# 140311_AriloTX_REV2_0_0.net
KiCad netlist of a schematic drawn in EAGLE
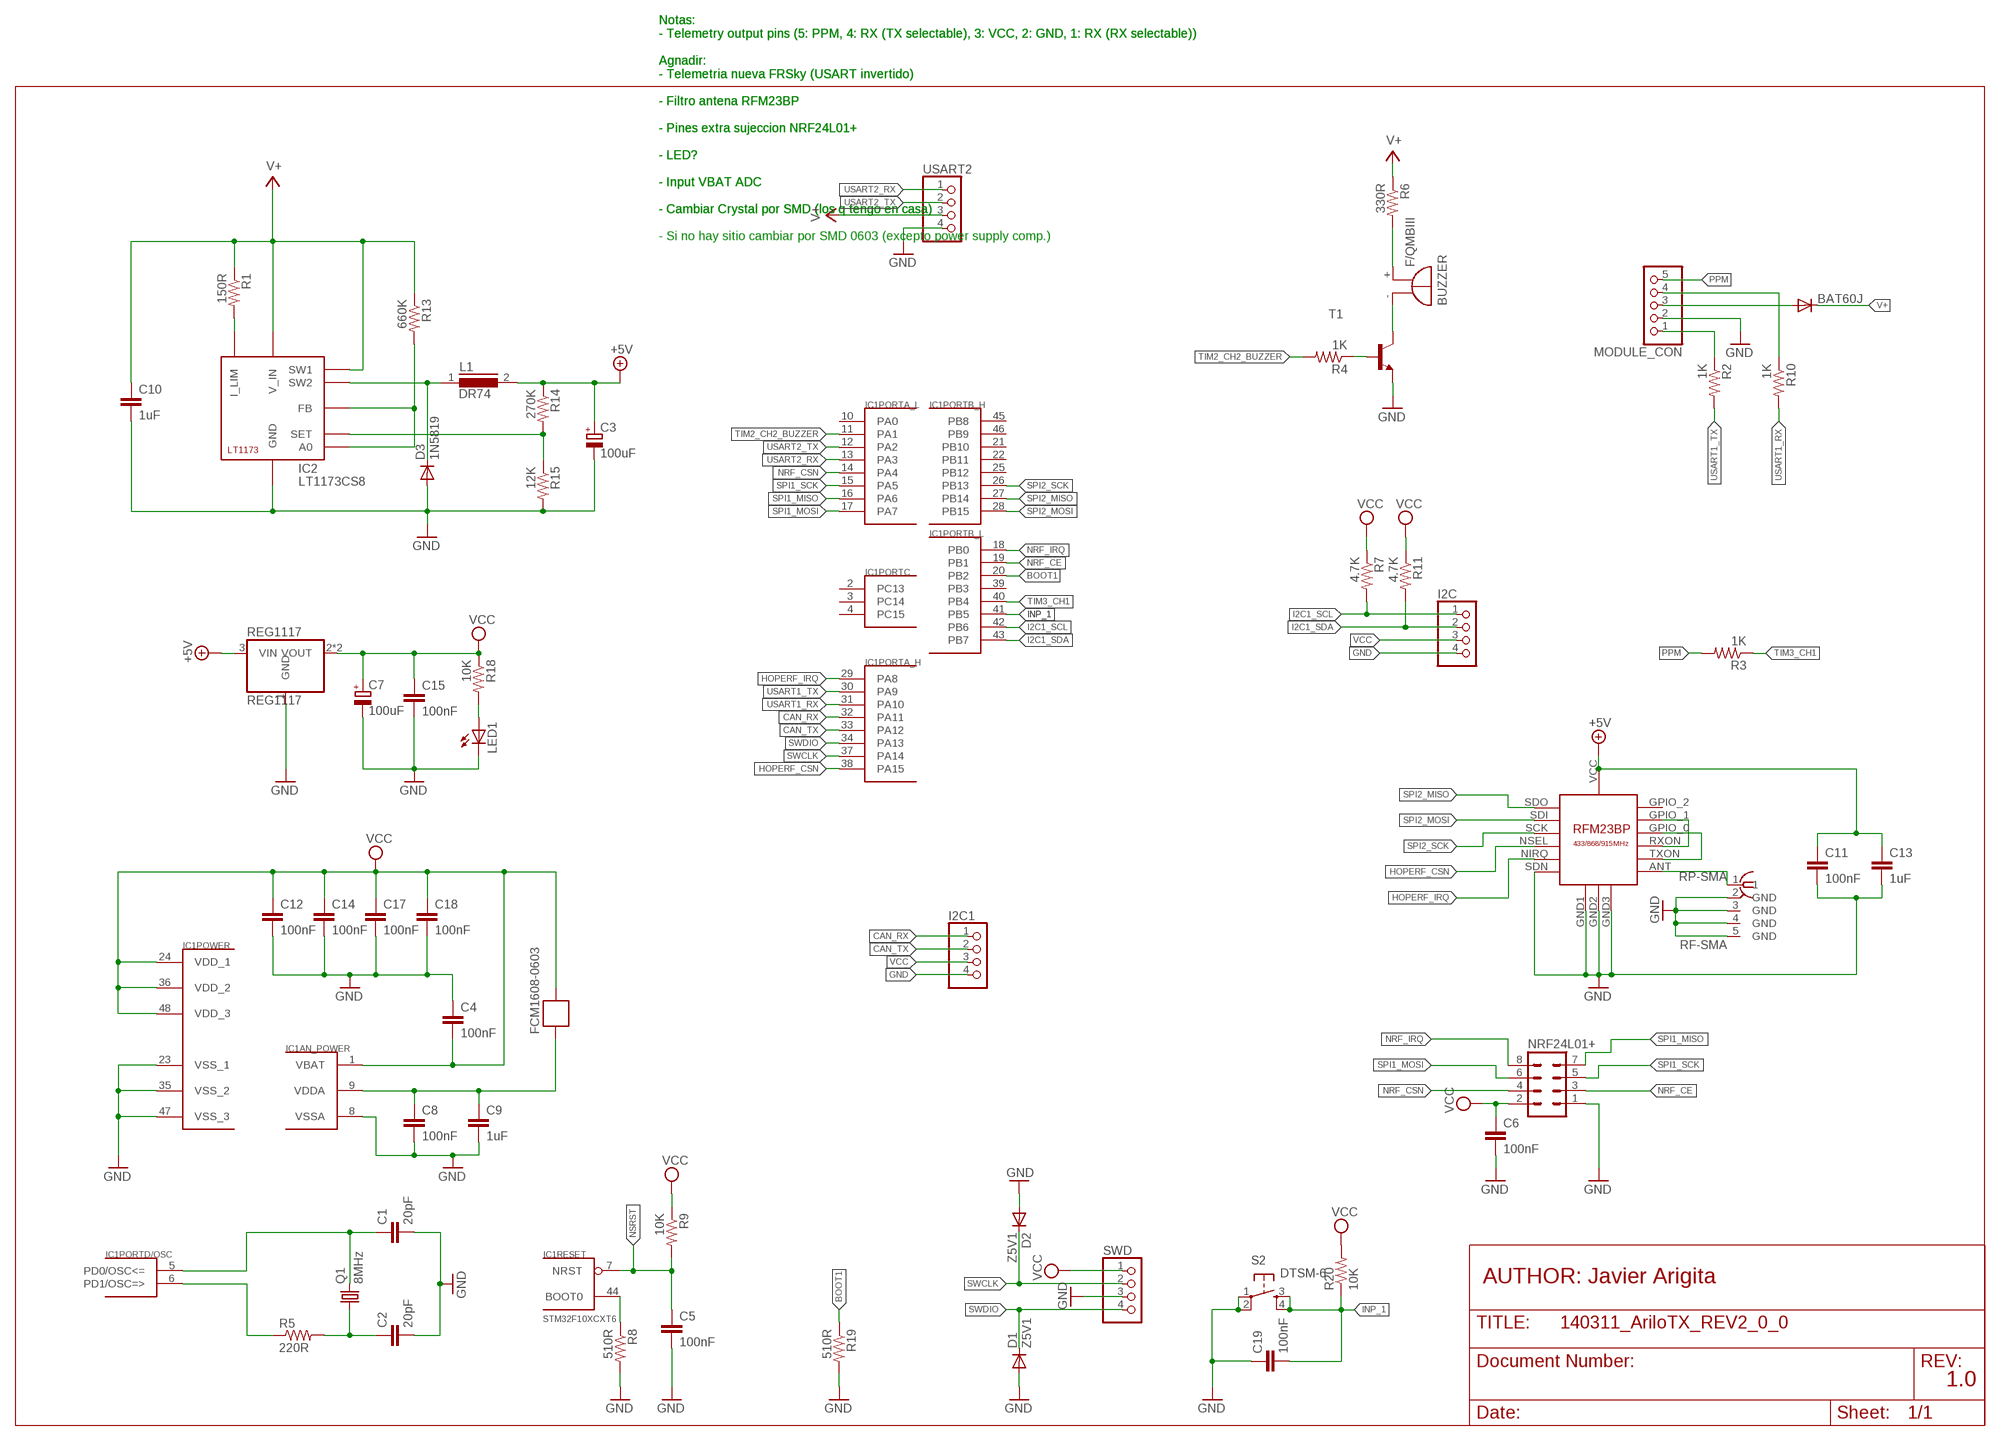
[diagram p0: schematic, sheet 1]

(export (version "E")
  (design (tool "Eeschema 10.0.6"))
  (components
    (comp (ref "BAT60J")
      (value "DIODE-SOD323-R")
      (footprint "eagle-import:SOD323-R")
      (libsource (lib "eagle-import") (part "DIODE-SOD323-R"))
    )
    (comp (ref "BUZZER")
      (value "F/QMBIII")
      (footprint "eagle-import:F_QMBIII")
      (libsource (lib "eagle-import") (part "F/QMBIII"))
    )
    (comp (ref "C1")
      (value "20pF")
      (footprint "eagle-import:C0805")
      (libsource (lib "eagle-import") (part "C-EUC0805"))
    )
    (comp (ref "C2")
      (value "20pF")
      (footprint "eagle-import:C0805")
      (libsource (lib "eagle-import") (part "C-EUC0805"))
    )
    (comp (ref "C3")
      (value "100uF")
      (footprint "eagle-import:SMC_B")
      (libsource (lib "eagle-import") (part "CPOL-EUSMCB"))
    )
    (comp (ref "C4")
      (value "100nF")
      (footprint "eagle-import:C0805")
      (libsource (lib "eagle-import") (part "C-EUC0805"))
    )
    (comp (ref "C5")
      (value "100nF")
      (footprint "eagle-import:C0805")
      (libsource (lib "eagle-import") (part "C-EUC0805"))
    )
    (comp (ref "C6")
      (value "100nF")
      (footprint "eagle-import:C0805")
      (libsource (lib "eagle-import") (part "C-EUC0805"))
    )
    (comp (ref "C7")
      (value "100uF")
      (footprint "eagle-import:SMC_B")
      (libsource (lib "eagle-import") (part "CPOL-EUSMCB"))
    )
    (comp (ref "C8")
      (value "100nF")
      (footprint "eagle-import:C0805")
      (libsource (lib "eagle-import") (part "C-EUC0805"))
    )
    (comp (ref "C9")
      (value "1uF")
      (footprint "eagle-import:C3216")
      (libsource (lib "eagle-import") (part "resistor_C-EUC3216"))
    )
    (comp (ref "C10")
      (value "1uF")
      (footprint "eagle-import:C3216")
      (libsource (lib "eagle-import") (part "resistor_C-EUC3216"))
    )
    (comp (ref "C11")
      (value "100nF")
      (footprint "eagle-import:C0805")
      (libsource (lib "eagle-import") (part "C-EUC0805"))
    )
    (comp (ref "C12")
      (value "100nF")
      (footprint "eagle-import:C0805")
      (libsource (lib "eagle-import") (part "C-EUC0805"))
    )
    (comp (ref "C13")
      (value "1uF")
      (footprint "eagle-import:C3216")
      (libsource (lib "eagle-import") (part "resistor_C-EUC3216"))
    )
    (comp (ref "C14")
      (value "100nF")
      (footprint "eagle-import:C0805")
      (libsource (lib "eagle-import") (part "C-EUC0805"))
    )
    (comp (ref "C15")
      (value "100nF")
      (footprint "eagle-import:C0805")
      (libsource (lib "eagle-import") (part "C-EUC0805"))
    )
    (comp (ref "C17")
      (value "100nF")
      (footprint "eagle-import:C0805")
      (libsource (lib "eagle-import") (part "C-EUC0805"))
    )
    (comp (ref "C18")
      (value "100nF")
      (footprint "eagle-import:C0805")
      (libsource (lib "eagle-import") (part "C-EUC0805"))
    )
    (comp (ref "C19")
      (value "100nF")
      (footprint "eagle-import:C0805")
      (libsource (lib "eagle-import") (part "C-EUC0805"))
    )
    (comp (ref "D1")
      (value "Z5V1")
      (footprint "eagle-import:SOD323-R")
      (libsource (lib "eagle-import") (part "DIODE-SOD323-R"))
    )
    (comp (ref "D2")
      (value "Z5V1")
      (footprint "eagle-import:SOD323-R")
      (libsource (lib "eagle-import") (part "DIODE-SOD323-R"))
    )
    (comp (ref "D3")
      (value "1N5819")
      (footprint "eagle-import:DO214AC")
      (libsource (lib "eagle-import") (part "DIODE-DO214AC"))
    )
    (comp (ref "FCM1608-0603")
      (value "FERRITE-BEAD")
      (footprint "eagle-import:R0603")
      (libsource (lib "eagle-import") (part "FERRITE-BEAD"))
    )
    (comp (ref "I2C")
      (value "PINHD-1X4")
      (footprint "eagle-import:1X04")
      (libsource (lib "eagle-import") (part "PINHD-1X4"))
    )
    (comp (ref "I2C1")
      (value "PINHD-1X4")
      (footprint "eagle-import:1X04")
      (libsource (lib "eagle-import") (part "PINHD-1X4"))
    )
    (comp (ref "IC1")
      (value "STM32F10XCXT6")
      (footprint "eagle-import:TQFP48")
      (libsource (lib "eagle-import") (part "STM32F10XCXT6"))
    )
    (comp (ref "IC2")
      (value "LT1173CS8")
      (footprint "eagle-import:SOIC8")
      (libsource (lib "eagle-import") (part "LT1173CS8"))
    )
    (comp (ref "L1")
      (value "DR74")
      (footprint "eagle-import:DR74")
      (libsource (lib "eagle-import") (part "DR74"))
    )
    (comp (ref "LED1")
      (value "LED0805")
      (footprint "eagle-import:CHIPLED_0805")
      (libsource (lib "eagle-import") (part "LED0805"))
    )
    (comp (ref "MODULE_CON")
      (value "PINHD-1X5")
      (footprint "eagle-import:1X05")
      (libsource (lib "eagle-import") (part "PINHD-1X5"))
    )
    (comp (ref "NRF24L01+")
      (value "MA04-2")
      (footprint "eagle-import:MA04-2")
      (libsource (lib "eagle-import") (part "MA04-2"))
    )
    (comp (ref "Q1")
      (value "8MHz")
      (footprint "eagle-import:SM49")
      (libsource (lib "eagle-import") (part "CRYSTALSM49"))
    )
    (comp (ref "R1")
      (value "150R")
      (footprint "eagle-import:R0805")
      (libsource (lib "eagle-import") (part "RESISTOR0805"))
    )
    (comp (ref "R2")
      (value "1K")
      (footprint "eagle-import:R0805")
      (libsource (lib "eagle-import") (part "RESISTOR0805"))
    )
    (comp (ref "R3")
      (value "1K")
      (footprint "eagle-import:R0805")
      (libsource (lib "eagle-import") (part "RESISTOR0805"))
    )
    (comp (ref "R4")
      (value "1K")
      (footprint "eagle-import:R0805")
      (libsource (lib "eagle-import") (part "RESISTOR0805"))
    )
    (comp (ref "R5")
      (value "220R")
      (footprint "eagle-import:R0805")
      (libsource (lib "eagle-import") (part "RESISTOR0805"))
    )
    (comp (ref "R6")
      (value "330R")
      (footprint "eagle-import:R0805")
      (libsource (lib "eagle-import") (part "RESISTOR0805"))
    )
    (comp (ref "R7")
      (value "4.7K")
      (footprint "eagle-import:R0805")
      (libsource (lib "eagle-import") (part "RESISTOR0805"))
    )
    (comp (ref "R8")
      (value "510R")
      (footprint "eagle-import:R0805")
      (libsource (lib "eagle-import") (part "RESISTOR0805"))
    )
    (comp (ref "R9")
      (value "10K")
      (footprint "eagle-import:R0805")
      (libsource (lib "eagle-import") (part "RESISTOR0805"))
    )
    (comp (ref "R10")
      (value "1K")
      (footprint "eagle-import:R0805")
      (libsource (lib "eagle-import") (part "RESISTOR0805"))
    )
    (comp (ref "R11")
      (value "4.7K")
      (footprint "eagle-import:R0805")
      (libsource (lib "eagle-import") (part "RESISTOR0805"))
    )
    (comp (ref "R13")
      (value "660K")
      (footprint "eagle-import:R0805")
      (libsource (lib "eagle-import") (part "RESISTOR0805"))
    )
    (comp (ref "R14")
      (value "270K")
      (footprint "eagle-import:R0805")
      (libsource (lib "eagle-import") (part "RESISTOR0805"))
    )
    (comp (ref "R15")
      (value "12K")
      (footprint "eagle-import:R0805")
      (libsource (lib "eagle-import") (part "RESISTOR0805"))
    )
    (comp (ref "R18")
      (value "10K")
      (footprint "eagle-import:R0805")
      (libsource (lib "eagle-import") (part "RESISTOR0805"))
    )
    (comp (ref "R19")
      (value "510R")
      (footprint "eagle-import:R0805")
      (libsource (lib "eagle-import") (part "RESISTOR0805"))
    )
    (comp (ref "R20")
      (value "10K")
      (footprint "eagle-import:R0805")
      (libsource (lib "eagle-import") (part "RESISTOR0805"))
    )
    (comp (ref "REG1117")
      (value "REG1117")
      (footprint "eagle-import:SOT223")
      (libsource (lib "eagle-import") (part "REG1117"))
    )
    (comp (ref "RP-SMA")
      (value "RF-SMA")
      (footprint "eagle-import:BU-SMA-H")
      (libsource (lib "eagle-import") (part "RF-SMA"))
    )
    (comp (ref "S2")
      (value "DTSM-6")
      (footprint "eagle-import:DTSM-6")
      (libsource (lib "eagle-import") (part "DTSM-6"))
    )
    (comp (ref "SWD")
      (value "PINHD-1X4")
      (footprint "eagle-import:1X04")
      (libsource (lib "eagle-import") (part "PINHD-1X4"))
    )
    (comp (ref "T1")
      (value "BC848-NPN-SOT23-BEC")
      (footprint "eagle-import:SOT23-BEC")
      (libsource (lib "eagle-import") (part "-NPN-SOT23-BECBC848"))
    )
    (comp (ref "U$1")
      (value "RFM23BP")
      (footprint "eagle-import:RFM23BP")
      (libsource (lib "eagle-import") (part "RFM23BP"))
    )
    (comp (ref "USART2")
      (value "PINHD-1X4")
      (footprint "eagle-import:1X04")
      (libsource (lib "eagle-import") (part "PINHD-1X4"))
    )
  )
  (nets
    (net (code "1") (name "+5V") (class "Default")
      (node (ref "C11") (pin "1") (pinfunction "1_1") (pintype "passive"))
      (node (ref "C13") (pin "1") (pinfunction "1_1") (pintype "passive"))
      (node (ref "C3") (pin "+") (pinfunction "+_+") (pintype "passive"))
      (node (ref "L1") (pin "2") (pinfunction "2_2") (pintype "passive"))
      (node (ref "R14") (pin "1") (pinfunction "1_1") (pintype "passive"))
      (node (ref "REG1117") (pin "3") (pinfunction "VIN_3") (pintype "input"))
      (node (ref "U$1") (pin "VCC") (pinfunction "VCC_VCC") (pintype "power_in"))
    )
    (net (code "2") (name "BOOT1") (class "Default")
      (node (ref "IC1") (pin "20") (pinfunction "PB2_20") (pintype "bidirectional"))
      (node (ref "R19") (pin "1") (pinfunction "1_1") (pintype "passive"))
    )
    (net (code "3") (name "CAN_RX") (class "Default")
      (node (ref "I2C1") (pin "1") (pinfunction "1_1") (pintype "passive"))
      (node (ref "IC1") (pin "32") (pinfunction "PA11_32") (pintype "bidirectional"))
    )
    (net (code "4") (name "CAN_TX") (class "Default")
      (node (ref "I2C1") (pin "2") (pinfunction "2_2") (pintype "passive"))
      (node (ref "IC1") (pin "33") (pinfunction "PA12_33") (pintype "bidirectional"))
    )
    (net (code "5") (name "GND") (class "Default")
      (node (ref "C1") (pin "2") (pinfunction "2_2") (pintype "passive"))
      (node (ref "C10") (pin "2") (pinfunction "2_2") (pintype "passive"))
      (node (ref "C11") (pin "2") (pinfunction "2_2") (pintype "passive"))
      (node (ref "C12") (pin "2") (pinfunction "2_2") (pintype "passive"))
      (node (ref "C13") (pin "2") (pinfunction "2_2") (pintype "passive"))
      (node (ref "C14") (pin "2") (pinfunction "2_2") (pintype "passive"))
      (node (ref "C15") (pin "2") (pinfunction "2_2") (pintype "passive"))
      (node (ref "C17") (pin "2") (pinfunction "2_2") (pintype "passive"))
      (node (ref "C18") (pin "2") (pinfunction "2_2") (pintype "passive"))
      (node (ref "C19") (pin "1") (pinfunction "1_1") (pintype "passive"))
      (node (ref "C2") (pin "2") (pinfunction "2_2") (pintype "passive"))
      (node (ref "C3") (pin "-") (pinfunction "-_-") (pintype "passive"))
      (node (ref "C4") (pin "1") (pinfunction "1_1") (pintype "passive"))
      (node (ref "C5") (pin "2") (pinfunction "2_2") (pintype "passive"))
      (node (ref "C6") (pin "2") (pinfunction "2_2") (pintype "passive"))
      (node (ref "C7") (pin "-") (pinfunction "-_-") (pintype "passive"))
      (node (ref "C8") (pin "2") (pinfunction "2_2") (pintype "passive"))
      (node (ref "C9") (pin "2") (pinfunction "2_2") (pintype "passive"))
      (node (ref "D1") (pin "A") (pinfunction "A_A") (pintype "passive"))
      (node (ref "D2") (pin "A") (pinfunction "A_A") (pintype "passive"))
      (node (ref "D3") (pin "A") (pinfunction "A_A") (pintype "passive"))
      (node (ref "I2C") (pin "4") (pinfunction "4_4") (pintype "passive"))
      (node (ref "I2C1") (pin "4") (pinfunction "4_4") (pintype "passive"))
      (node (ref "IC1") (pin "23") (pinfunction "VSS_1_23") (pintype "power_in"))
      (node (ref "IC1") (pin "35") (pinfunction "VSS_2_35") (pintype "power_in"))
      (node (ref "IC1") (pin "47") (pinfunction "VSS_3_47") (pintype "power_in"))
      (node (ref "IC1") (pin "8") (pinfunction "VSSA_8") (pintype "power_in"))
      (node (ref "IC2") (pin "5") (pinfunction "GND_5") (pintype "power_in"))
      (node (ref "LED1") (pin "C") (pinfunction "C_C") (pintype "passive"))
      (node (ref "MODULE_CON") (pin "2") (pinfunction "2_2") (pintype "passive"))
      (node (ref "NRF24L01+") (pin "1") (pinfunction "1_1") (pintype "passive"))
      (node (ref "R15") (pin "2") (pinfunction "2_2") (pintype "passive"))
      (node (ref "R19") (pin "2") (pinfunction "2_2") (pintype "passive"))
      (node (ref "R8") (pin "2") (pinfunction "2_2") (pintype "passive"))
      (node (ref "REG1117") (pin "1") (pinfunction "GND_1") (pintype "power_in"))
      (node (ref "RP-SMA") (pin "2") (pinfunction "GND_2") (pintype "power_in"))
      (node (ref "RP-SMA") (pin "3") (pinfunction "GND_3") (pintype "bidirectional"))
      (node (ref "RP-SMA") (pin "4") (pinfunction "GND_4") (pintype "bidirectional"))
      (node (ref "RP-SMA") (pin "5") (pinfunction "GND_5") (pintype "bidirectional"))
      (node (ref "S2") (pin "1") (pinfunction "1_1") (pintype "passive"))
      (node (ref "S2") (pin "2") (pinfunction "2_2") (pintype "passive"))
      (node (ref "SWD") (pin "3") (pinfunction "3_3") (pintype "passive"))
      (node (ref "T1") (pin "E") (pinfunction "E_E") (pintype "passive"))
      (node (ref "U$1") (pin "GND1") (pinfunction "GND1_GND1") (pintype "power_in"))
      (node (ref "U$1") (pin "GND2") (pinfunction "GND2_GND2") (pintype "power_in"))
      (node (ref "U$1") (pin "GND3") (pinfunction "GND3_GND3") (pintype "power_in"))
      (node (ref "U$1") (pin "SDN") (pinfunction "SDN_SDN") (pintype "bidirectional"))
      (node (ref "USART2") (pin "4") (pinfunction "4_4") (pintype "passive"))
    )
    (net (code "6") (name "HOPERF_CSN") (class "Default")
      (node (ref "IC1") (pin "38") (pinfunction "PA15_38") (pintype "bidirectional"))
      (node (ref "U$1") (pin "NSEL") (pinfunction "NSEL_NSEL") (pintype "bidirectional"))
    )
    (net (code "7") (name "HOPERF_IRQ") (class "Default")
      (node (ref "IC1") (pin "29") (pinfunction "PA8_29") (pintype "bidirectional"))
      (node (ref "U$1") (pin "NIRQ") (pinfunction "NIRQ_NIRQ") (pintype "bidirectional"))
    )
    (net (code "8") (name "I2C1_SCL") (class "Default")
      (node (ref "I2C") (pin "1") (pinfunction "1_1") (pintype "passive"))
      (node (ref "IC1") (pin "42") (pinfunction "PB6_42") (pintype "bidirectional"))
      (node (ref "R7") (pin "2") (pinfunction "2_2") (pintype "passive"))
    )
    (net (code "9") (name "I2C1_SDA") (class "Default")
      (node (ref "I2C") (pin "2") (pinfunction "2_2") (pintype "passive"))
      (node (ref "IC1") (pin "43") (pinfunction "PB7_43") (pintype "bidirectional"))
      (node (ref "R11") (pin "2") (pinfunction "2_2") (pintype "passive"))
    )
    (net (code "10") (name "INP_1") (class "Default")
      (node (ref "C19") (pin "2") (pinfunction "2_2") (pintype "passive"))
      (node (ref "IC1") (pin "41") (pinfunction "PB5_41") (pintype "bidirectional"))
      (node (ref "R20") (pin "1") (pinfunction "1_1") (pintype "passive"))
      (node (ref "S2") (pin "3") (pinfunction "3_3") (pintype "passive"))
      (node (ref "S2") (pin "4") (pinfunction "4_4") (pintype "passive"))
    )
    (net (code "11") (name "NRF_CE") (class "Default")
      (node (ref "IC1") (pin "19") (pinfunction "PB1_19") (pintype "bidirectional"))
      (node (ref "NRF24L01+") (pin "3") (pinfunction "3_3") (pintype "passive"))
    )
    (net (code "12") (name "NRF_CSN") (class "Default")
      (node (ref "IC1") (pin "14") (pinfunction "PA4_14") (pintype "bidirectional"))
      (node (ref "NRF24L01+") (pin "4") (pinfunction "4_4") (pintype "passive"))
    )
    (net (code "13") (name "NRF_IRQ") (class "Default")
      (node (ref "IC1") (pin "18") (pinfunction "PB0_18") (pintype "bidirectional"))
      (node (ref "NRF24L01+") (pin "8") (pinfunction "8_8") (pintype "passive"))
    )
    (net (code "14") (name "NSRST") (class "Default")
      (node (ref "C5") (pin "1") (pinfunction "1_1") (pintype "passive"))
      (node (ref "IC1") (pin "7") (pinfunction "NRST_7") (pintype "input"))
      (node (ref "R9") (pin "2") (pinfunction "2_2") (pintype "passive"))
    )
    (net (code "15") (name "Net-(BAT60J-PadA)") (class "Default")
      (node (ref "BAT60J") (pin "A") (pinfunction "A_A") (pintype "passive"))
      (node (ref "MODULE_CON") (pin "3") (pinfunction "3_3") (pintype "passive"))
    )
    (net (code "16") (name "Net-(BUZZER-+)") (class "Default")
      (node (ref "BUZZER") (pin "-") (pinfunction "+_-") (pintype "passive"))
      (node (ref "T1") (pin "C") (pinfunction "C_C") (pintype "passive"))
    )
    (net (code "17") (name "Net-(BUZZER--)") (class "Default")
      (node (ref "BUZZER") (pin "+") (pinfunction "-_+") (pintype "passive"))
      (node (ref "R6") (pin "2") (pinfunction "2_2") (pintype "passive"))
    )
    (net (code "18") (name "Net-(C2-Pad1)") (class "Default")
      (node (ref "C2") (pin "1") (pinfunction "1_1") (pintype "passive"))
      (node (ref "Q1") (pin "1") (pinfunction "1_1") (pintype "passive"))
      (node (ref "R5") (pin "2") (pinfunction "2_2") (pintype "passive"))
    )
    (net (code "19") (name "Net-(FCM1608-0603-P$2)") (class "Default")
      (node (ref "C8") (pin "1") (pinfunction "1_1") (pintype "passive"))
      (node (ref "C9") (pin "1") (pinfunction "1_1") (pintype "passive"))
      (node (ref "FCM1608-0603") (pin "2") (pinfunction "P$2_2") (pintype "bidirectional"))
      (node (ref "IC1") (pin "9") (pinfunction "VDDA_9") (pintype "power_in"))
    )
    (net (code "20") (name "Net-(IC1G-PD0{slash}OSC<=)") (class "Default")
      (node (ref "C1") (pin "1") (pinfunction "1_1") (pintype "passive"))
      (node (ref "IC1") (pin "5") (pinfunction "PD0/OSC<=_5") (pintype "bidirectional"))
      (node (ref "Q1") (pin "2") (pinfunction "2_2") (pintype "passive"))
    )
    (net (code "21") (name "Net-(IC1G-PD1{slash}OSC=>)") (class "Default")
      (node (ref "IC1") (pin "6") (pinfunction "PD1/OSC=>_6") (pintype "bidirectional"))
      (node (ref "R5") (pin "1") (pinfunction "1_1") (pintype "passive"))
    )
    (net (code "22") (name "Net-(IC1I-BOOT0)") (class "Default")
      (node (ref "IC1") (pin "44") (pinfunction "BOOT0_44") (pintype "input"))
      (node (ref "R8") (pin "1") (pinfunction "1_1") (pintype "passive"))
    )
    (net (code "23") (name "Net-(IC2-A0)") (class "Default")
      (node (ref "IC2") (pin "6") (pinfunction "A0_6") (pintype "passive"))
      (node (ref "IC2") (pin "8") (pinfunction "FB_8") (pintype "passive"))
      (node (ref "R13") (pin "2") (pinfunction "2_2") (pintype "passive"))
    )
    (net (code "24") (name "Net-(IC2-I_LIM)") (class "Default")
      (node (ref "IC2") (pin "1") (pinfunction "I_LIM_1") (pintype "passive"))
      (node (ref "R1") (pin "2") (pinfunction "2_2") (pintype "passive"))
    )
    (net (code "25") (name "Net-(IC2-SET)") (class "Default")
      (node (ref "IC2") (pin "7") (pinfunction "SET_7") (pintype "passive"))
      (node (ref "R14") (pin "2") (pinfunction "2_2") (pintype "passive"))
      (node (ref "R15") (pin "1") (pinfunction "1_1") (pintype "passive"))
    )
    (net (code "26") (name "Net-(IC2-SW2)") (class "Default")
      (node (ref "D3") (pin "C") (pinfunction "C_C") (pintype "passive"))
      (node (ref "IC2") (pin "4") (pinfunction "SW2_4") (pintype "passive"))
      (node (ref "L1") (pin "1") (pinfunction "1_1") (pintype "passive"))
    )
    (net (code "27") (name "Net-(LED1-PadA)") (class "Default")
      (node (ref "LED1") (pin "A") (pinfunction "A_A") (pintype "passive"))
      (node (ref "R18") (pin "2") (pinfunction "2_2") (pintype "passive"))
    )
    (net (code "28") (name "Net-(MODULE_CON-Pad1)") (class "Default")
      (node (ref "MODULE_CON") (pin "1") (pinfunction "1_1") (pintype "passive"))
      (node (ref "R2") (pin "1") (pinfunction "1_1") (pintype "passive"))
    )
    (net (code "29") (name "Net-(MODULE_CON-Pad4)") (class "Default")
      (node (ref "MODULE_CON") (pin "4") (pinfunction "4_4") (pintype "passive"))
      (node (ref "R10") (pin "1") (pinfunction "1_1") (pintype "passive"))
    )
    (net (code "30") (name "Net-(R4-Pad1)") (class "Default")
      (node (ref "R4") (pin "1") (pinfunction "1_1") (pintype "passive"))
      (node (ref "T1") (pin "B") (pinfunction "B_B") (pintype "passive"))
    )
    (net (code "31") (name "Net-(RP-SMA-Pad1)") (class "Default")
      (node (ref "RP-SMA") (pin "1") (pinfunction "1_1") (pintype "passive"))
      (node (ref "U$1") (pin "ANT") (pinfunction "ANT_ANT") (pintype "bidirectional"))
    )
    (net (code "32") (name "Net-(U$1-PadGPIO_0)") (class "Default")
      (node (ref "U$1") (pin "GPIO_0") (pinfunction "GPIO_0_GPIO_0") (pintype "bidirectional"))
      (node (ref "U$1") (pin "TXON") (pinfunction "TXON_TXON") (pintype "bidirectional"))
    )
    (net (code "33") (name "Net-(U$1-PadGPIO_1)") (class "Default")
      (node (ref "U$1") (pin "GPIO_1") (pinfunction "GPIO_1_GPIO_1") (pintype "bidirectional"))
      (node (ref "U$1") (pin "RXON") (pinfunction "RXON_RXON") (pintype "bidirectional"))
    )
    (net (code "34") (name "PPM") (class "Default")
      (node (ref "MODULE_CON") (pin "5") (pinfunction "5_5") (pintype "passive"))
      (node (ref "R3") (pin "2") (pinfunction "2_2") (pintype "passive"))
    )
    (net (code "35") (name "SPI1_MISO") (class "Default")
      (node (ref "IC1") (pin "16") (pinfunction "PA6_16") (pintype "bidirectional"))
      (node (ref "NRF24L01+") (pin "7") (pinfunction "7_7") (pintype "passive"))
    )
    (net (code "36") (name "SPI1_MOSI") (class "Default")
      (node (ref "IC1") (pin "17") (pinfunction "PA7_17") (pintype "bidirectional"))
      (node (ref "NRF24L01+") (pin "6") (pinfunction "6_6") (pintype "passive"))
    )
    (net (code "37") (name "SPI1_SCK") (class "Default")
      (node (ref "IC1") (pin "15") (pinfunction "PA5_15") (pintype "bidirectional"))
      (node (ref "NRF24L01+") (pin "5") (pinfunction "5_5") (pintype "passive"))
    )
    (net (code "38") (name "SPI2_MISO") (class "Default")
      (node (ref "IC1") (pin "27") (pinfunction "PB14_27") (pintype "bidirectional"))
      (node (ref "U$1") (pin "SDO") (pinfunction "SDO_SDO") (pintype "bidirectional"))
    )
    (net (code "39") (name "SPI2_MOSI") (class "Default")
      (node (ref "IC1") (pin "28") (pinfunction "PB15_28") (pintype "bidirectional"))
      (node (ref "U$1") (pin "SDI") (pinfunction "SDI_SDI") (pintype "bidirectional"))
    )
    (net (code "40") (name "SPI2_SCK") (class "Default")
      (node (ref "IC1") (pin "26") (pinfunction "PB13_26") (pintype "bidirectional"))
      (node (ref "U$1") (pin "SCK") (pinfunction "SCK_SCK") (pintype "bidirectional"))
    )
    (net (code "41") (name "SWCLK") (class "Default")
      (node (ref "D2") (pin "C") (pinfunction "C_C") (pintype "passive"))
      (node (ref "IC1") (pin "37") (pinfunction "PA14_37") (pintype "bidirectional"))
      (node (ref "SWD") (pin "2") (pinfunction "2_2") (pintype "passive"))
    )
    (net (code "42") (name "SWDIO") (class "Default")
      (node (ref "D1") (pin "C") (pinfunction "C_C") (pintype "passive"))
      (node (ref "IC1") (pin "34") (pinfunction "PA13_34") (pintype "bidirectional"))
      (node (ref "SWD") (pin "4") (pinfunction "4_4") (pintype "passive"))
    )
    (net (code "43") (name "TIM2_CH2_BUZZER") (class "Default")
      (node (ref "IC1") (pin "11") (pinfunction "PA1_11") (pintype "bidirectional"))
      (node (ref "R4") (pin "2") (pinfunction "2_2") (pintype "passive"))
    )
    (net (code "44") (name "TIM3_CH1") (class "Default")
      (node (ref "IC1") (pin "40") (pinfunction "PB4_40") (pintype "bidirectional"))
      (node (ref "R3") (pin "1") (pinfunction "1_1") (pintype "passive"))
    )
    (net (code "45") (name "USART1_RX") (class "Default")
      (node (ref "IC1") (pin "31") (pinfunction "PA10_31") (pintype "bidirectional"))
      (node (ref "R10") (pin "2") (pinfunction "2_2") (pintype "passive"))
    )
    (net (code "46") (name "USART1_TX") (class "Default")
      (node (ref "IC1") (pin "30") (pinfunction "PA9_30") (pintype "bidirectional"))
      (node (ref "R2") (pin "2") (pinfunction "2_2") (pintype "passive"))
    )
    (net (code "47") (name "USART2_RX") (class "Default")
      (node (ref "IC1") (pin "13") (pinfunction "PA3_13") (pintype "bidirectional"))
      (node (ref "USART2") (pin "1") (pinfunction "1_1") (pintype "passive"))
    )
    (net (code "48") (name "USART2_TX") (class "Default")
      (node (ref "IC1") (pin "12") (pinfunction "PA2_12") (pintype "bidirectional"))
      (node (ref "USART2") (pin "2") (pinfunction "2_2") (pintype "passive"))
    )
    (net (code "49") (name "V+") (class "Default")
      (node (ref "BAT60J") (pin "C") (pinfunction "C_C") (pintype "passive"))
      (node (ref "C10") (pin "1") (pinfunction "1_1") (pintype "passive"))
      (node (ref "IC2") (pin "2") (pinfunction "V_IN_2") (pintype "passive"))
      (node (ref "IC2") (pin "3") (pinfunction "SW1_3") (pintype "passive"))
      (node (ref "R1") (pin "1") (pinfunction "1_1") (pintype "passive"))
      (node (ref "R13") (pin "1") (pinfunction "1_1") (pintype "passive"))
      (node (ref "R6") (pin "1") (pinfunction "1_1") (pintype "passive"))
      (node (ref "USART2") (pin "3") (pinfunction "3_3") (pintype "passive"))
    )
    (net (code "50") (name "VCC") (class "Default")
      (node (ref "C12") (pin "1") (pinfunction "1_1") (pintype "passive"))
      (node (ref "C14") (pin "1") (pinfunction "1_1") (pintype "passive"))
      (node (ref "C15") (pin "1") (pinfunction "1_1") (pintype "passive"))
      (node (ref "C17") (pin "1") (pinfunction "1_1") (pintype "passive"))
      (node (ref "C18") (pin "1") (pinfunction "1_1") (pintype "passive"))
      (node (ref "C4") (pin "2") (pinfunction "2_2") (pintype "passive"))
      (node (ref "C6") (pin "1") (pinfunction "1_1") (pintype "passive"))
      (node (ref "C7") (pin "+") (pinfunction "+_+") (pintype "passive"))
      (node (ref "FCM1608-0603") (pin "1") (pinfunction "P$1_1") (pintype "bidirectional"))
      (node (ref "I2C") (pin "3") (pinfunction "3_3") (pintype "passive"))
      (node (ref "I2C1") (pin "3") (pinfunction "3_3") (pintype "passive"))
      (node (ref "IC1") (pin "1") (pinfunction "VBAT_1") (pintype "power_in"))
      (node (ref "IC1") (pin "24") (pinfunction "VDD_1_24") (pintype "power_in"))
      (node (ref "IC1") (pin "36") (pinfunction "VDD_2_36") (pintype "power_in"))
      (node (ref "IC1") (pin "48") (pinfunction "VDD_3_48") (pintype "power_in"))
      (node (ref "NRF24L01+") (pin "2") (pinfunction "2_2") (pintype "passive"))
      (node (ref "R11") (pin "1") (pinfunction "1_1") (pintype "passive"))
      (node (ref "R18") (pin "1") (pinfunction "1_1") (pintype "passive"))
      (node (ref "R20") (pin "2") (pinfunction "2_2") (pintype "passive"))
      (node (ref "R7") (pin "1") (pinfunction "1_1") (pintype "passive"))
      (node (ref "R9") (pin "1") (pinfunction "1_1") (pintype "passive"))
      (node (ref "REG1117") (pin "2") (pinfunction "VOUT_2") (pintype "power_in"))
      (node (ref "REG1117") (pin "4") (pinfunction "VOUT_4") (pintype "power_in"))
      (node (ref "SWD") (pin "1") (pinfunction "1_1") (pintype "passive"))
    )
    (net (code "51") (name "unconnected-(IC1C-PA0-Pad10)") (class "Default")
      (node (ref "IC1") (pin "10") (pinfunction "PA0_10") (pintype "bidirectional"))
    )
    (net (code "52") (name "unconnected-(IC1D-PB8-Pad45)") (class "Default")
      (node (ref "IC1") (pin "45") (pinfunction "PB8_45") (pintype "bidirectional"))
    )
    (net (code "53") (name "unconnected-(IC1D-PB9-Pad46)") (class "Default")
      (node (ref "IC1") (pin "46") (pinfunction "PB9_46") (pintype "bidirectional"))
    )
    (net (code "54") (name "unconnected-(IC1D-PB10-Pad21)") (class "Default")
      (node (ref "IC1") (pin "21") (pinfunction "PB10_21") (pintype "bidirectional"))
    )
    (net (code "55") (name "unconnected-(IC1D-PB11-Pad22)") (class "Default")
      (node (ref "IC1") (pin "22") (pinfunction "PB11_22") (pintype "bidirectional"))
    )
    (net (code "56") (name "unconnected-(IC1D-PB12-Pad25)") (class "Default")
      (node (ref "IC1") (pin "25") (pinfunction "PB12_25") (pintype "bidirectional"))
    )
    (net (code "57") (name "unconnected-(IC1E-PB3-Pad39)") (class "Default")
      (node (ref "IC1") (pin "39") (pinfunction "PB3_39") (pintype "bidirectional"))
    )
    (net (code "58") (name "unconnected-(IC1F-PC13-Pad2)") (class "Default")
      (node (ref "IC1") (pin "2") (pinfunction "PC13_2") (pintype "bidirectional"))
    )
    (net (code "59") (name "unconnected-(IC1F-PC14-Pad3)") (class "Default")
      (node (ref "IC1") (pin "3") (pinfunction "PC14_3") (pintype "bidirectional"))
    )
    (net (code "60") (name "unconnected-(IC1F-PC15-Pad4)") (class "Default")
      (node (ref "IC1") (pin "4") (pinfunction "PC15_4") (pintype "bidirectional"))
    )
    (net (code "61") (name "unconnected-(U$1-PadGPIO_2)") (class "Default")
      (node (ref "U$1") (pin "GPIO_2") (pinfunction "GPIO_2_GPIO_2") (pintype "bidirectional"))
    )
  )
)
